# SD_Reader.net
KiCad netlist of a schematic drawn in Altium Designer
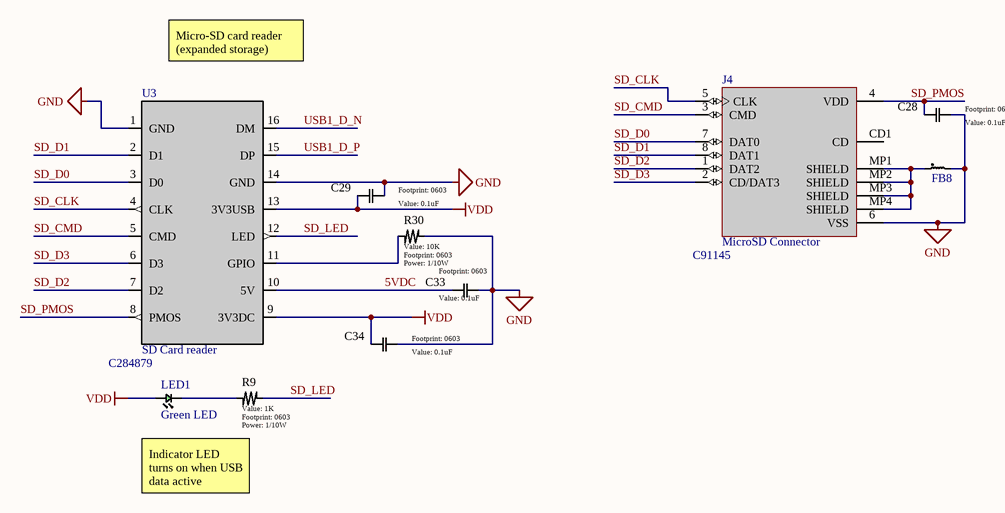
[diagram p0: SD_Reader.SchDoc]

(export (version "E")
  (design (tool "Eeschema 10.0.6"))
  (components
    (comp (ref "C28")
      (value "0.1uF")
      (footprint "0603")
      (fields
        (field (name "VOLTAGE") ">10V")
        (field (name "TOLERANCE") "10%")
        (field (name "Comment") "Generic Capacitor")
      )
      (libsource (lib "Capacitors") (part "Generic Capacitor"))
    )
    (comp (ref "C29")
      (value "0.1uF")
      (footprint "0603")
      (fields
        (field (name "VOLTAGE") ">10V")
        (field (name "TOLERANCE") "10%")
        (field (name "Comment") "Generic Capacitor")
      )
      (libsource (lib "Capacitors") (part "Generic Capacitor"))
    )
    (comp (ref "C33")
      (value "0.1uF")
      (footprint "0603")
      (fields
        (field (name "VOLTAGE") ">10V")
        (field (name "TOLERANCE") "10%")
        (field (name "Comment") "Generic Capacitor")
      )
      (libsource (lib "Capacitors") (part "Generic Capacitor"))
    )
    (comp (ref "C34")
      (value "0.1uF")
      (footprint "0603")
      (fields
        (field (name "VOLTAGE") ">10V")
        (field (name "TOLERANCE") "10%")
        (field (name "Comment") "Generic Capacitor")
      )
      (libsource (lib "Capacitors") (part "Generic Capacitor"))
    )
    (comp (ref "FB8")
      (value "C2971883; PE-0603FB121ST")
      (footprint "0603")
      (description "120 Ohms @ 100 MHz 1 Signal Line Ferrite Bead 0603 (1608 Metric) 500mA 180mOhm")
      (fields
        (field (name "MANUFACTURER") "Pulse")
        (field (name "MANUFACTURER PART NUMBER") "PE-0603FB121ST")
      )
      (libsource (lib "Inductors") (part "PE-0603FB121ST"))
    )
    (comp (ref "J4")
      (value "MicroSD Connector")
      (footprint "TF-01A")
      (description "Deck MicroSD card (TF card) Self bomb SMD SD Card Connector")
      (fields (field (name "LCSC PN") "C91145"))
      (libsource (lib "Connectors") (part "TF-01A"))
    )
    (comp (ref "LED1")
      (value "Green LED")
      (footprint "0603 (1608 Metric) Concave")
      (description "LED Uni-Color Green 574nm 2-Pin Chip LED T/R")
      (libsource (lib "Diodes") (part "LTST-C191KGKT"))
    )
    (comp (ref "R9")
      (value "1K")
      (footprint "0603")
      (fields
        (field (name "TOLERANCE") "1%")
        (field (name "POWER") "1/10W")
        (field (name "Comment") "Generic Resistor")
      )
      (libsource (lib "Resistors") (part "Generic Resistor"))
    )
    (comp (ref "R30")
      (value "10K")
      (footprint "0603")
      (fields
        (field (name "TOLERANCE") "1%")
        (field (name "POWER") "1/10W")
        (field (name "Comment") "Generic Resistor")
      )
      (libsource (lib "Resistors") (part "Generic Resistor"))
    )
    (comp (ref "U3")
      (value "SD Card reader")
      (footprint "SSOP-16-150mil")
      (description "USB 2.0 SD/MSPRO Card Reader Controller")
      (fields (field (name "LCSC PN") "C284879"))
      (libsource (lib "Misc ICs") (part "GL823K-HCY04"))
    )
  )
  (nets
    (net (code "1") (name "/5VDC") (class "Default")
      (node (ref "C33") (pin "2") (pinfunction "2_2") (pintype "passive"))
      (node (ref "U3") (pin "10") (pinfunction "5V_10") (pintype "power_in"))
    )
    (net (code "2") (name "/SD_CLK") (class "Default")
      (node (ref "J4") (pin "5") (pinfunction "CLK_5") (pintype "bidirectional"))
      (node (ref "U3") (pin "4") (pinfunction "CLK_4") (pintype "output"))
    )
    (net (code "3") (name "/SD_CMD") (class "Default")
      (node (ref "J4") (pin "3") (pinfunction "CMD_3") (pintype "bidirectional"))
      (node (ref "U3") (pin "5") (pinfunction "CMD_5") (pintype "bidirectional"))
    )
    (net (code "4") (name "/SD_D0") (class "Default")
      (node (ref "J4") (pin "7") (pinfunction "DAT0_7") (pintype "bidirectional"))
      (node (ref "U3") (pin "3") (pinfunction "D0_3") (pintype "bidirectional"))
    )
    (net (code "5") (name "/SD_D1") (class "Default")
      (node (ref "J4") (pin "8") (pinfunction "DAT1_8") (pintype "bidirectional"))
      (node (ref "U3") (pin "2") (pinfunction "D1_2") (pintype "bidirectional"))
    )
    (net (code "6") (name "/SD_D2") (class "Default")
      (node (ref "J4") (pin "1") (pinfunction "DAT2_1") (pintype "bidirectional"))
      (node (ref "U3") (pin "7") (pinfunction "D2_7") (pintype "bidirectional"))
    )
    (net (code "7") (name "/SD_D3") (class "Default")
      (node (ref "J4") (pin "2") (pinfunction "CD/DAT3_2") (pintype "bidirectional"))
      (node (ref "U3") (pin "6") (pinfunction "D3_6") (pintype "bidirectional"))
    )
    (net (code "8") (name "/SD_LED") (class "Default")
      (node (ref "R9") (pin "1") (pinfunction "1_1") (pintype "passive"))
      (node (ref "U3") (pin "12") (pinfunction "LED_12") (pintype "output"))
    )
    (net (code "9") (name "/SD_PMOS") (class "Default")
      (node (ref "C28") (pin "2") (pinfunction "2_2") (pintype "passive"))
      (node (ref "J4") (pin "4") (pinfunction "VDD_4") (pintype "power_in"))
      (node (ref "U3") (pin "8") (pinfunction "PMOS_8") (pintype "output"))
    )
    (net (code "10") (name "/USB1_D_N") (class "Default")
      (node (ref "U3") (pin "16") (pinfunction "DM_16") (pintype "bidirectional"))
    )
    (net (code "11") (name "/USB1_D_P") (class "Default")
      (node (ref "U3") (pin "15") (pinfunction "DP_15") (pintype "bidirectional"))
    )
    (net (code "12") (name "GND") (class "Default")
      (node (ref "C28") (pin "1") (pinfunction "1_1") (pintype "passive"))
      (node (ref "C29") (pin "1") (pinfunction "1_1") (pintype "passive"))
      (node (ref "C33") (pin "1") (pinfunction "1_1") (pintype "passive"))
      (node (ref "C34") (pin "1") (pinfunction "1_1") (pintype "passive"))
      (node (ref "FB8") (pin "2") (pinfunction "2_2") (pintype "passive"))
      (node (ref "J4") (pin "6") (pinfunction "VSS_6") (pintype "power_in"))
      (node (ref "R30") (pin "1") (pinfunction "1_1") (pintype "passive"))
      (node (ref "U3") (pin "1") (pinfunction "GND_1") (pintype "power_in"))
      (node (ref "U3") (pin "14") (pinfunction "GND_14") (pintype "power_in"))
    )
    (net (code "13") (name "Net-(FB8-Pad1)") (class "Default")
      (node (ref "FB8") (pin "1") (pinfunction "1_1") (pintype "passive"))
      (node (ref "J4") (pin "MP1") (pinfunction "SHIELD_MP1") (pintype "power_in"))
      (node (ref "J4") (pin "MP2") (pinfunction "SHIELD_MP2") (pintype "power_in"))
      (node (ref "J4") (pin "MP3") (pinfunction "SHIELD_MP3") (pintype "power_in"))
      (node (ref "J4") (pin "MP4") (pinfunction "SHIELD_MP4") (pintype "power_in"))
    )
    (net (code "14") (name "Net-(LED1-Cathode)") (class "Default")
      (node (ref "LED1") (pin "1") (pinfunction "Cathode_1") (pintype "passive"))
      (node (ref "R9") (pin "2") (pinfunction "2_2") (pintype "passive"))
    )
    (net (code "15") (name "Net-(U3-GPIO)") (class "Default")
      (node (ref "R30") (pin "2") (pinfunction "2_2") (pintype "passive"))
      (node (ref "U3") (pin "11") (pinfunction "GPIO_11") (pintype "bidirectional"))
    )
    (net (code "16") (name "VDD") (class "Default")
      (node (ref "C29") (pin "2") (pinfunction "2_2") (pintype "passive"))
      (node (ref "C34") (pin "2") (pinfunction "2_2") (pintype "passive"))
      (node (ref "LED1") (pin "2") (pinfunction "Anode_2") (pintype "passive"))
      (node (ref "U3") (pin "13") (pinfunction "3V3USB_13") (pintype "power_in"))
      (node (ref "U3") (pin "9") (pinfunction "3V3DC_9") (pintype "power_in"))
    )
    (net (code "17") (name "unconnected-(J4-CD-PadCD1)") (class "Default")
      (node (ref "J4") (pin "CD1") (pinfunction "CD_CD1") (pintype "passive"))
    )
  )
)
